# 1-Schematic_ESP_nand.net
KiCad netlist of a schematic drawn in EasyEDA
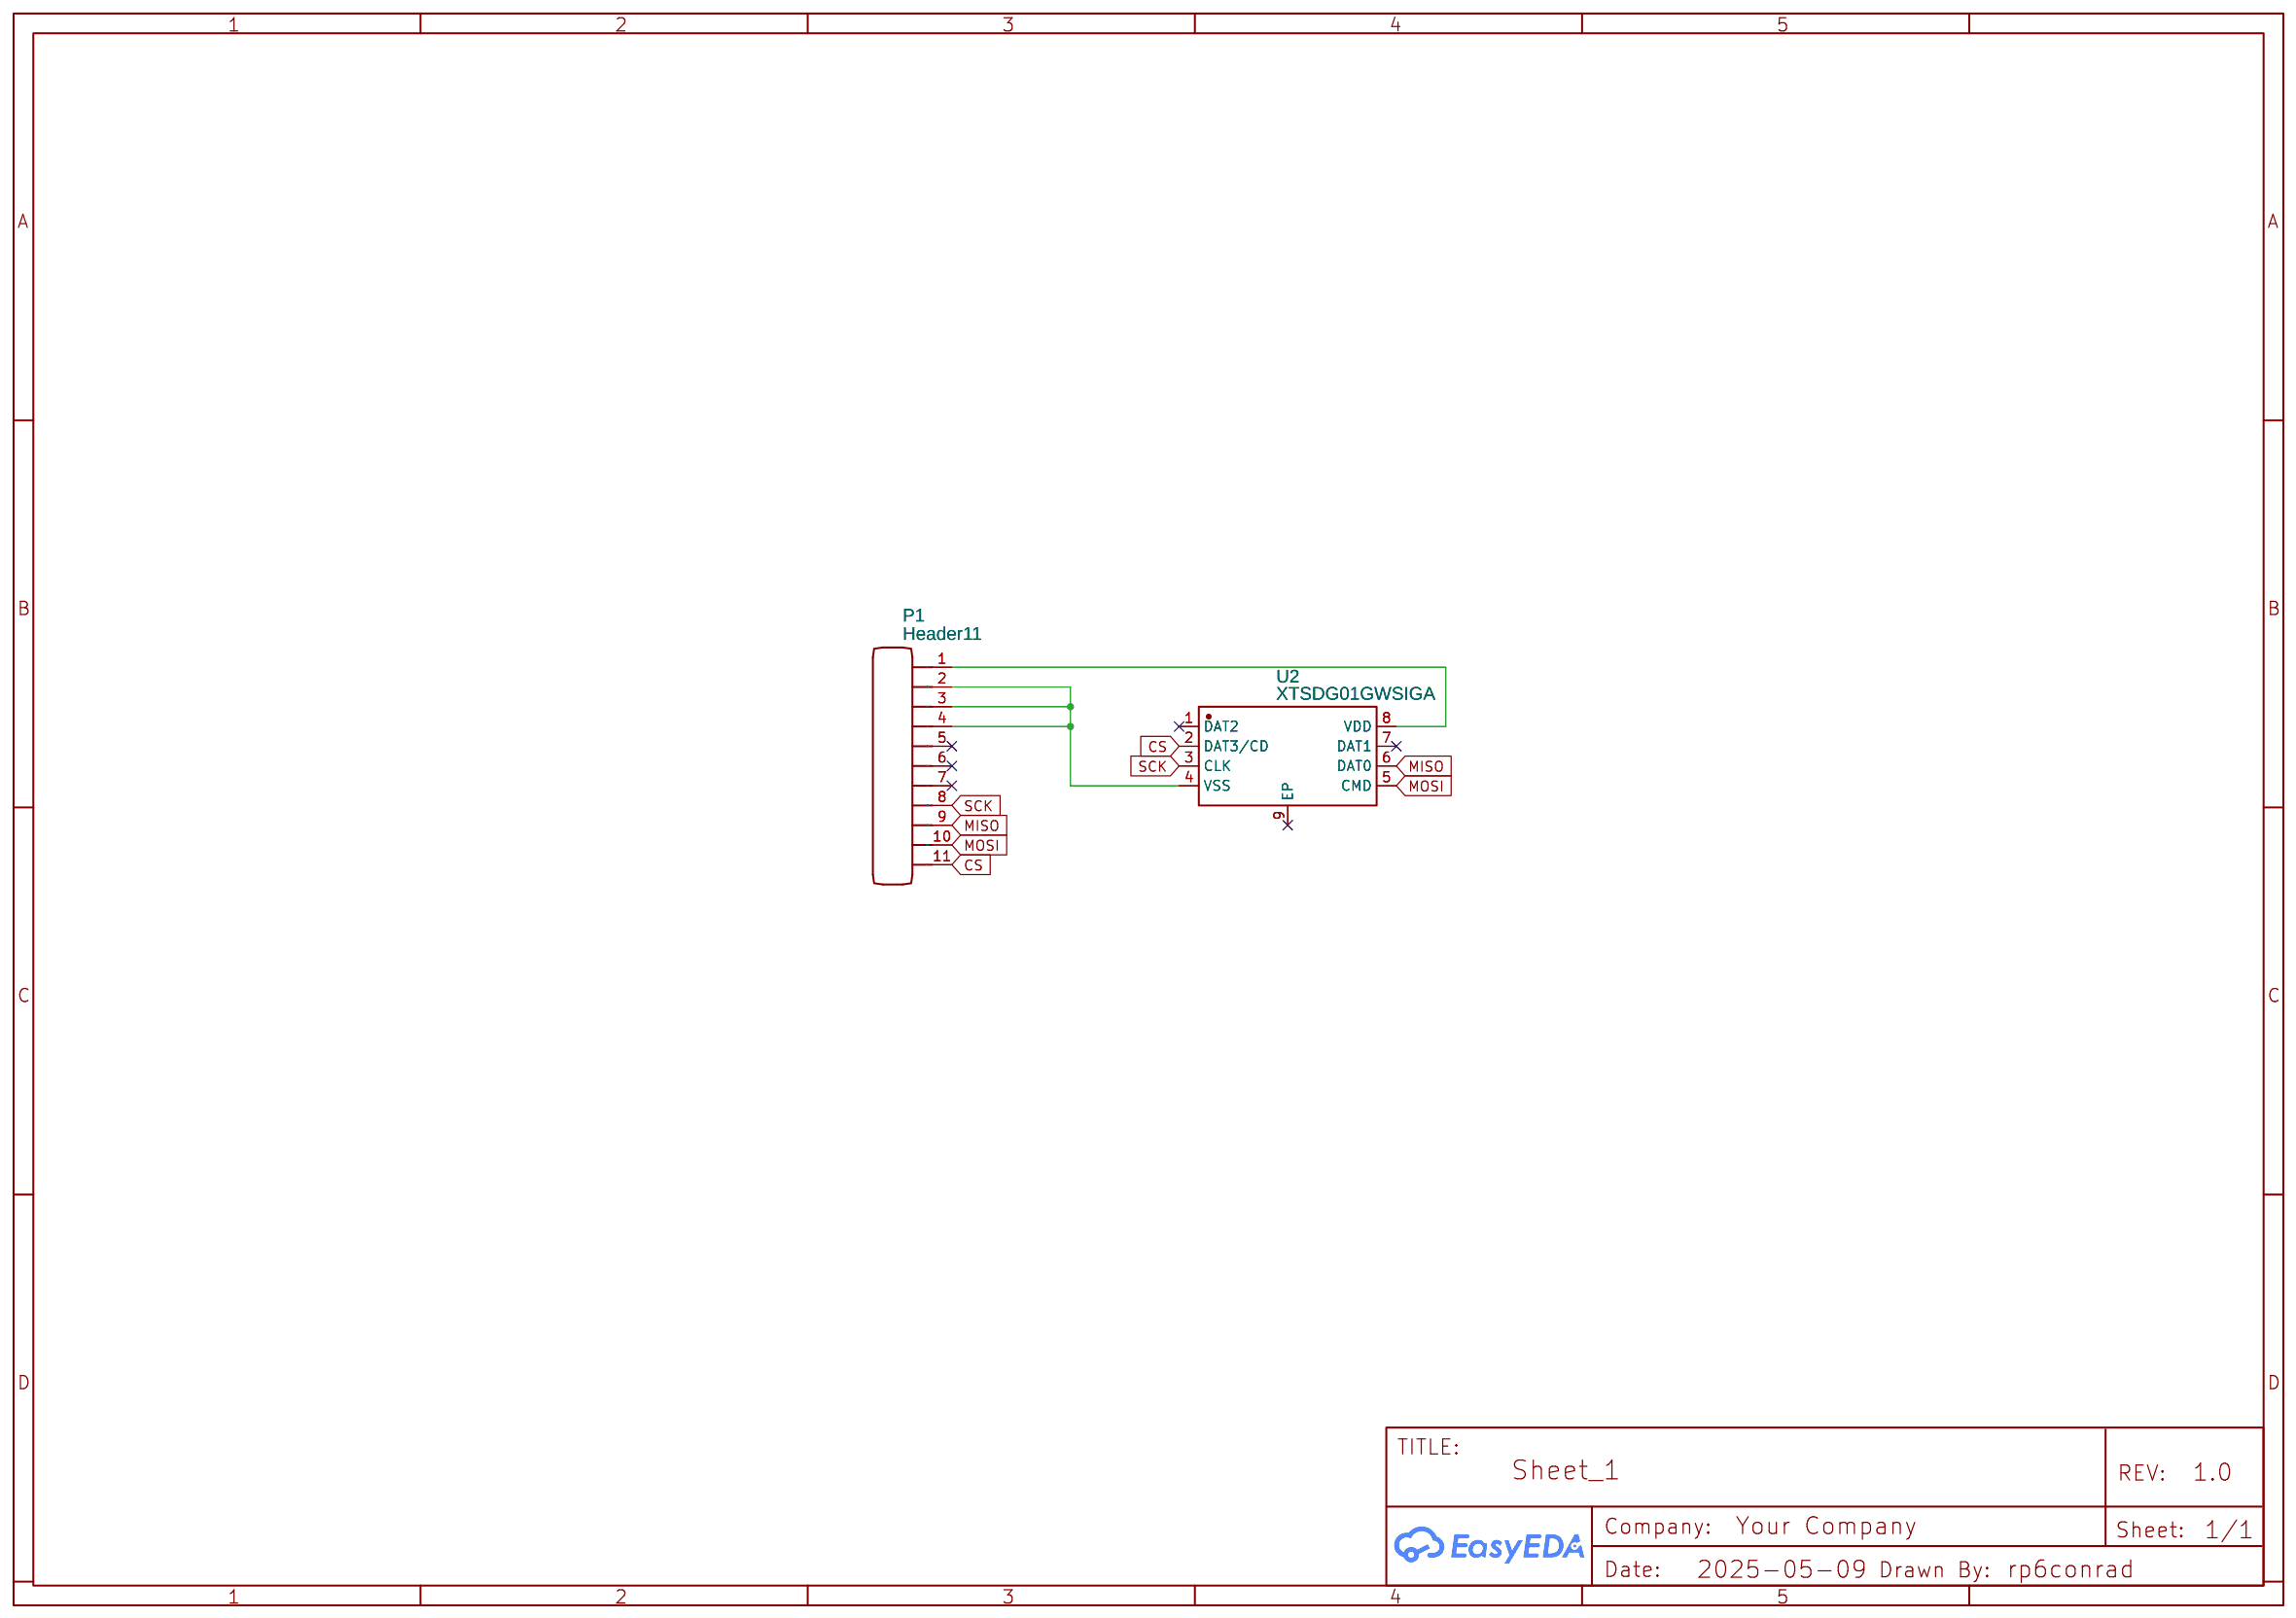
[diagram p0: schematic sheet]

(export (version "E")
  (design (tool "Eeschema 10.0.6"))
  (components
    (comp (ref "P1") (value "Header11") (libsource (lib "") (part "Header11")))
    (comp (ref "U2")
      (value "XTSDG01GWSIGA")
      (fields (field (name "Manufacturer") "XTX(芯天下)"))
      (libsource (lib "") (part "XTSDG01GWSIGA"))
    )
  )
  (nets
    (net (code "1") (name "CS") (class "Default")
      (node (ref "P1") (pin "11") (pinfunction "11_11") (pintype "unspecified"))
      (node (ref "U2") (pin "2") (pinfunction "DAT3/CD_2") (pintype "unspecified"))
    )
    (net (code "2") (name "MISO") (class "Default")
      (node (ref "P1") (pin "9") (pinfunction "9_9") (pintype "unspecified"))
      (node (ref "U2") (pin "6") (pinfunction "DAT0_6") (pintype "unspecified"))
    )
    (net (code "3") (name "MOSI") (class "Default")
      (node (ref "P1") (pin "10") (pinfunction "10_10") (pintype "unspecified"))
      (node (ref "U2") (pin "5") (pinfunction "CMD_5") (pintype "unspecified"))
    )
    (net (code "4") (name "Net-(U2-VDD)") (class "Default")
      (node (ref "P1") (pin "1") (pinfunction "1_1") (pintype "unspecified"))
      (node (ref "U2") (pin "8") (pinfunction "VDD_8") (pintype "unspecified"))
    )
    (net (code "5") (name "Net-(U2-VSS)") (class "Default")
      (node (ref "P1") (pin "2") (pinfunction "2_2") (pintype "unspecified"))
      (node (ref "P1") (pin "3") (pinfunction "3_3") (pintype "unspecified"))
      (node (ref "P1") (pin "4") (pinfunction "4_4") (pintype "unspecified"))
      (node (ref "U2") (pin "4") (pinfunction "VSS_4") (pintype "unspecified"))
    )
    (net (code "6") (name "SCK") (class "Default")
      (node (ref "P1") (pin "8") (pinfunction "8_8") (pintype "unspecified"))
      (node (ref "U2") (pin "3") (pinfunction "CLK_3") (pintype "unspecified"))
    )
    (net (code "7") (name "unconnected-(P1-Pad5)") (class "Default")
      (node (ref "P1") (pin "5") (pinfunction "5_5") (pintype "unspecified+no_connect"))
    )
    (net (code "8") (name "unconnected-(P1-Pad6)") (class "Default")
      (node (ref "P1") (pin "6") (pinfunction "6_6") (pintype "unspecified+no_connect"))
    )
    (net (code "9") (name "unconnected-(P1-Pad7)") (class "Default")
      (node (ref "P1") (pin "7") (pinfunction "7_7") (pintype "unspecified+no_connect"))
    )
    (net (code "10") (name "unconnected-(U2-DAT1-Pad7)") (class "Default")
      (node (ref "U2") (pin "7") (pinfunction "DAT1_7") (pintype "unspecified+no_connect"))
    )
    (net (code "11") (name "unconnected-(U2-DAT2-Pad1)") (class "Default")
      (node (ref "U2") (pin "1") (pinfunction "DAT2_1") (pintype "unspecified+no_connect"))
    )
    (net (code "12") (name "unconnected-(U2-EP-Pad9)") (class "Default")
      (node (ref "U2") (pin "9") (pinfunction "EP_9") (pintype "unspecified+no_connect"))
    )
  )
)
